# AMS1117.net
KiCad netlist of a schematic drawn in Altium Designer
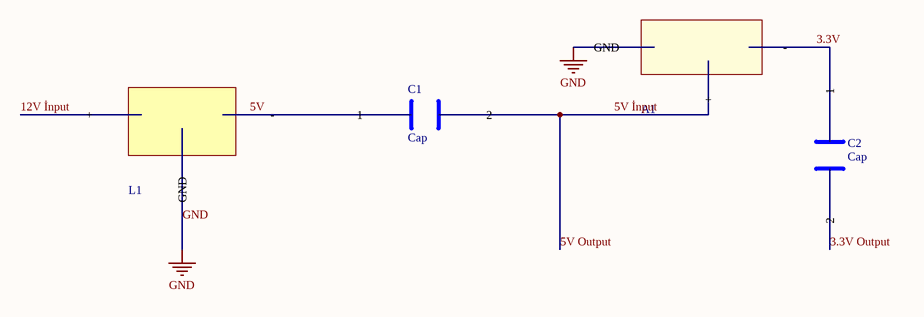
[diagram p0: AMS1117.SchDoc]

(export (version "E")
  (design (tool "Eeschema 10.0.6"))
  (components
    (comp (ref "A1")
      (value "AMSRegülatör")
      (footprint "AMS1117-3,3")
      (description "Crimper, Wire Special For 16740")
      (fields
        (field (name "MANUFACTURER") "Advanced Monolithic Systems")
        (field (name "MANUFACTURER PART NUMBER") "AMS1117-3.3")
      )
      (libsource (lib "RegülatorKütüphane") (part "AMS1117-3.3"))
    )
    (comp (ref "C1")
      (value "Cap")
      (footprint "Cap1")
      (description "CAPACITOR POLY FILM FILM 0.1UF, 5%, 63V,")
      (fields
        (field (name "MANUFACTURER") "KEMET")
        (field (name "MANUFACTURER PART NUMBER") "R82DC3100DQ50J")
      )
      (libsource (lib "RegülatorKütüphane") (part "R82DC3100DQ50J"))
    )
    (comp (ref "C2")
      (value "Cap")
      (footprint "Cap1")
      (description "CAPACITOR POLY FILM FILM 0.1UF, 5%, 63V,")
      (fields
        (field (name "MANUFACTURER") "KEMET")
        (field (name "MANUFACTURER PART NUMBER") "R82DC3100DQ50J")
      )
      (libsource (lib "RegülatorKütüphane") (part "R82DC3100DQ50J"))
    )
    (comp (ref "L1")
      (value "LMRegülatör")
      (footprint "LM7805")
      (description "Series 3-Terminal Positive Regulators")
      (fields
        (field (name "MANUFACTURER") "Texas Instruments")
        (field (name "MANUFACTURER PART NUMBER") "LM7805CT/NOPB")
      )
      (libsource (lib "RegülatorKütüphane") (part "LM7805CT/NOPB"))
    )
  )
  (nets
    (net (code "1") (name "/3.3V") (class "Default")
      (node (ref "A1") (pin "-") (pinfunction "-_-") (pintype "passive"))
      (node (ref "C2") (pin "1") (pinfunction "1_1") (pintype "passive"))
    )
    (net (code "2") (name "/3.3V Output") (class "Default")
      (node (ref "C2") (pin "2") (pinfunction "2_2") (pintype "passive"))
    )
    (net (code "3") (name "/5V") (class "Default")
      (node (ref "C1") (pin "1") (pinfunction "1_1") (pintype "passive"))
      (node (ref "L1") (pin "-") (pinfunction "-_-") (pintype "passive"))
    )
    (net (code "4") (name "/5V Output") (class "Default")
      (node (ref "A1") (pin "+") (pinfunction "+_+") (pintype "passive"))
      (node (ref "C1") (pin "2") (pinfunction "2_2") (pintype "passive"))
    )
    (net (code "5") (name "/12V İnput") (class "Default")
      (node (ref "L1") (pin "+") (pinfunction "+_+") (pintype "passive"))
    )
    (net (code "6") (name "GND") (class "Default")
      (node (ref "A1") (pin "GND") (pinfunction "GND_GND") (pintype "passive"))
      (node (ref "L1") (pin "GND") (pinfunction "GND_GND") (pintype "passive"))
    )
  )
)
